# OctoSlime_Base_Unit_Light.net
KiCad netlist of a schematic drawn in EasyEDA Pro
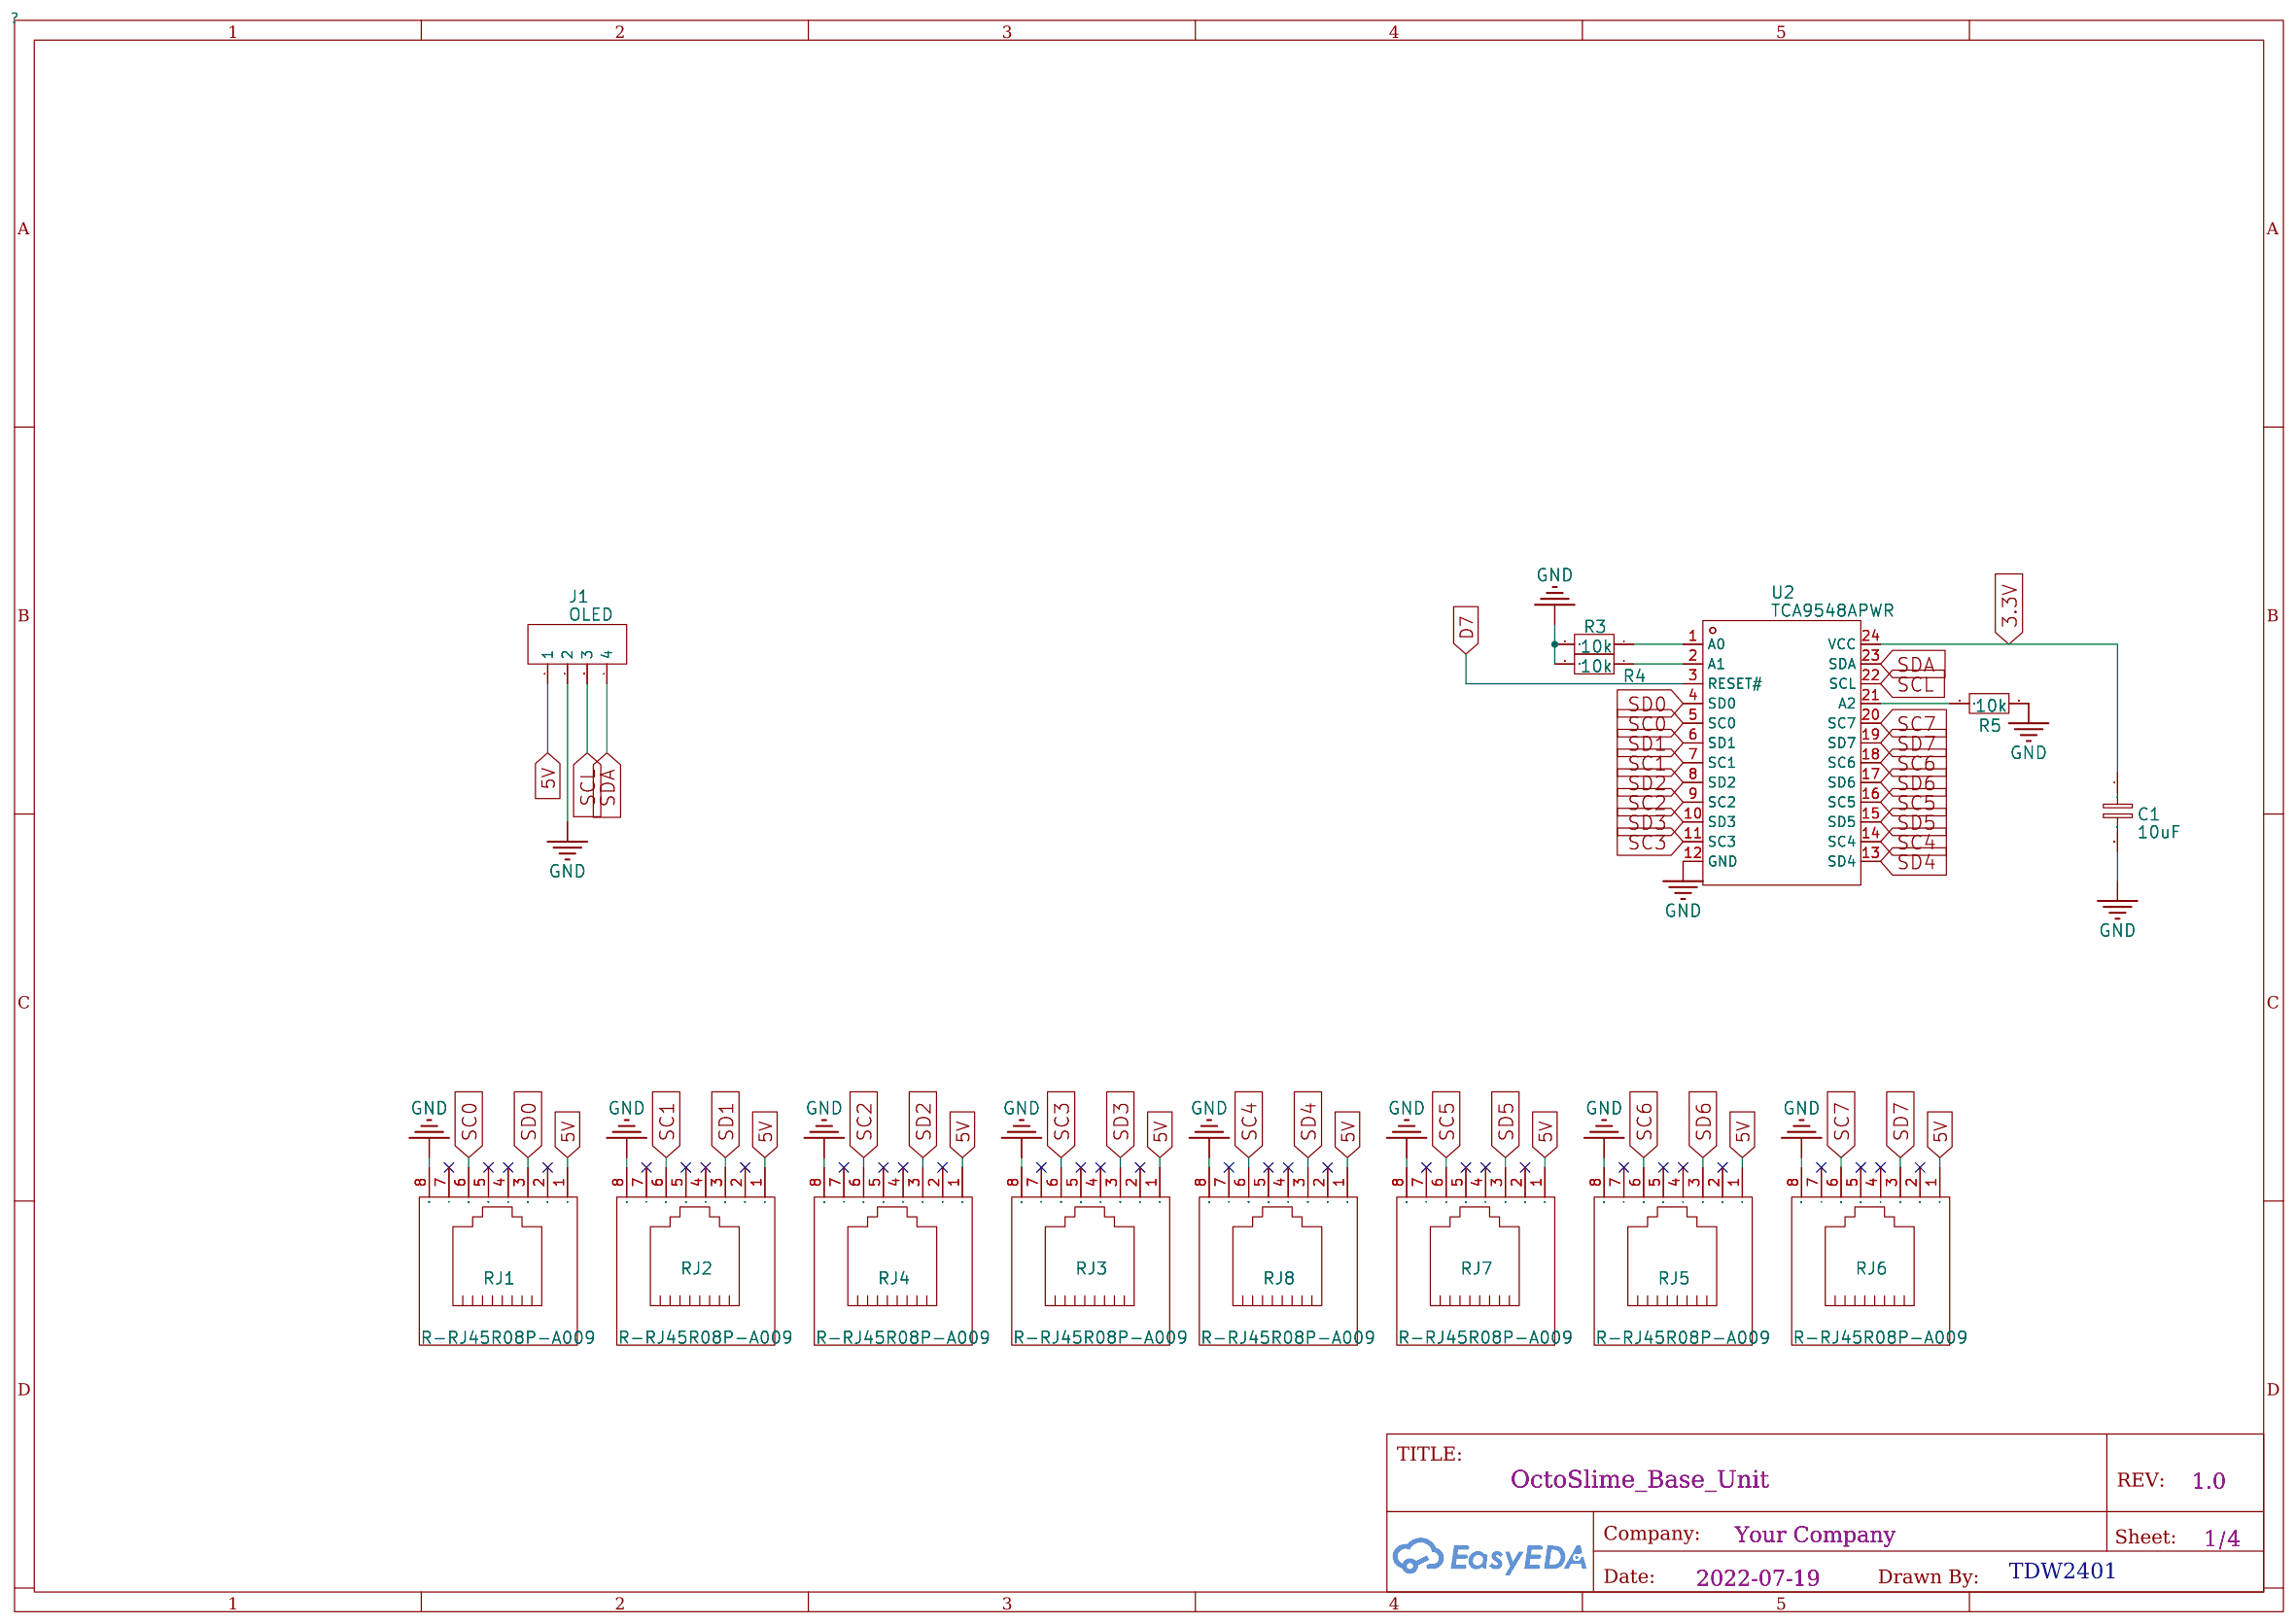
[diagram p0: I2C breakout and OLED]
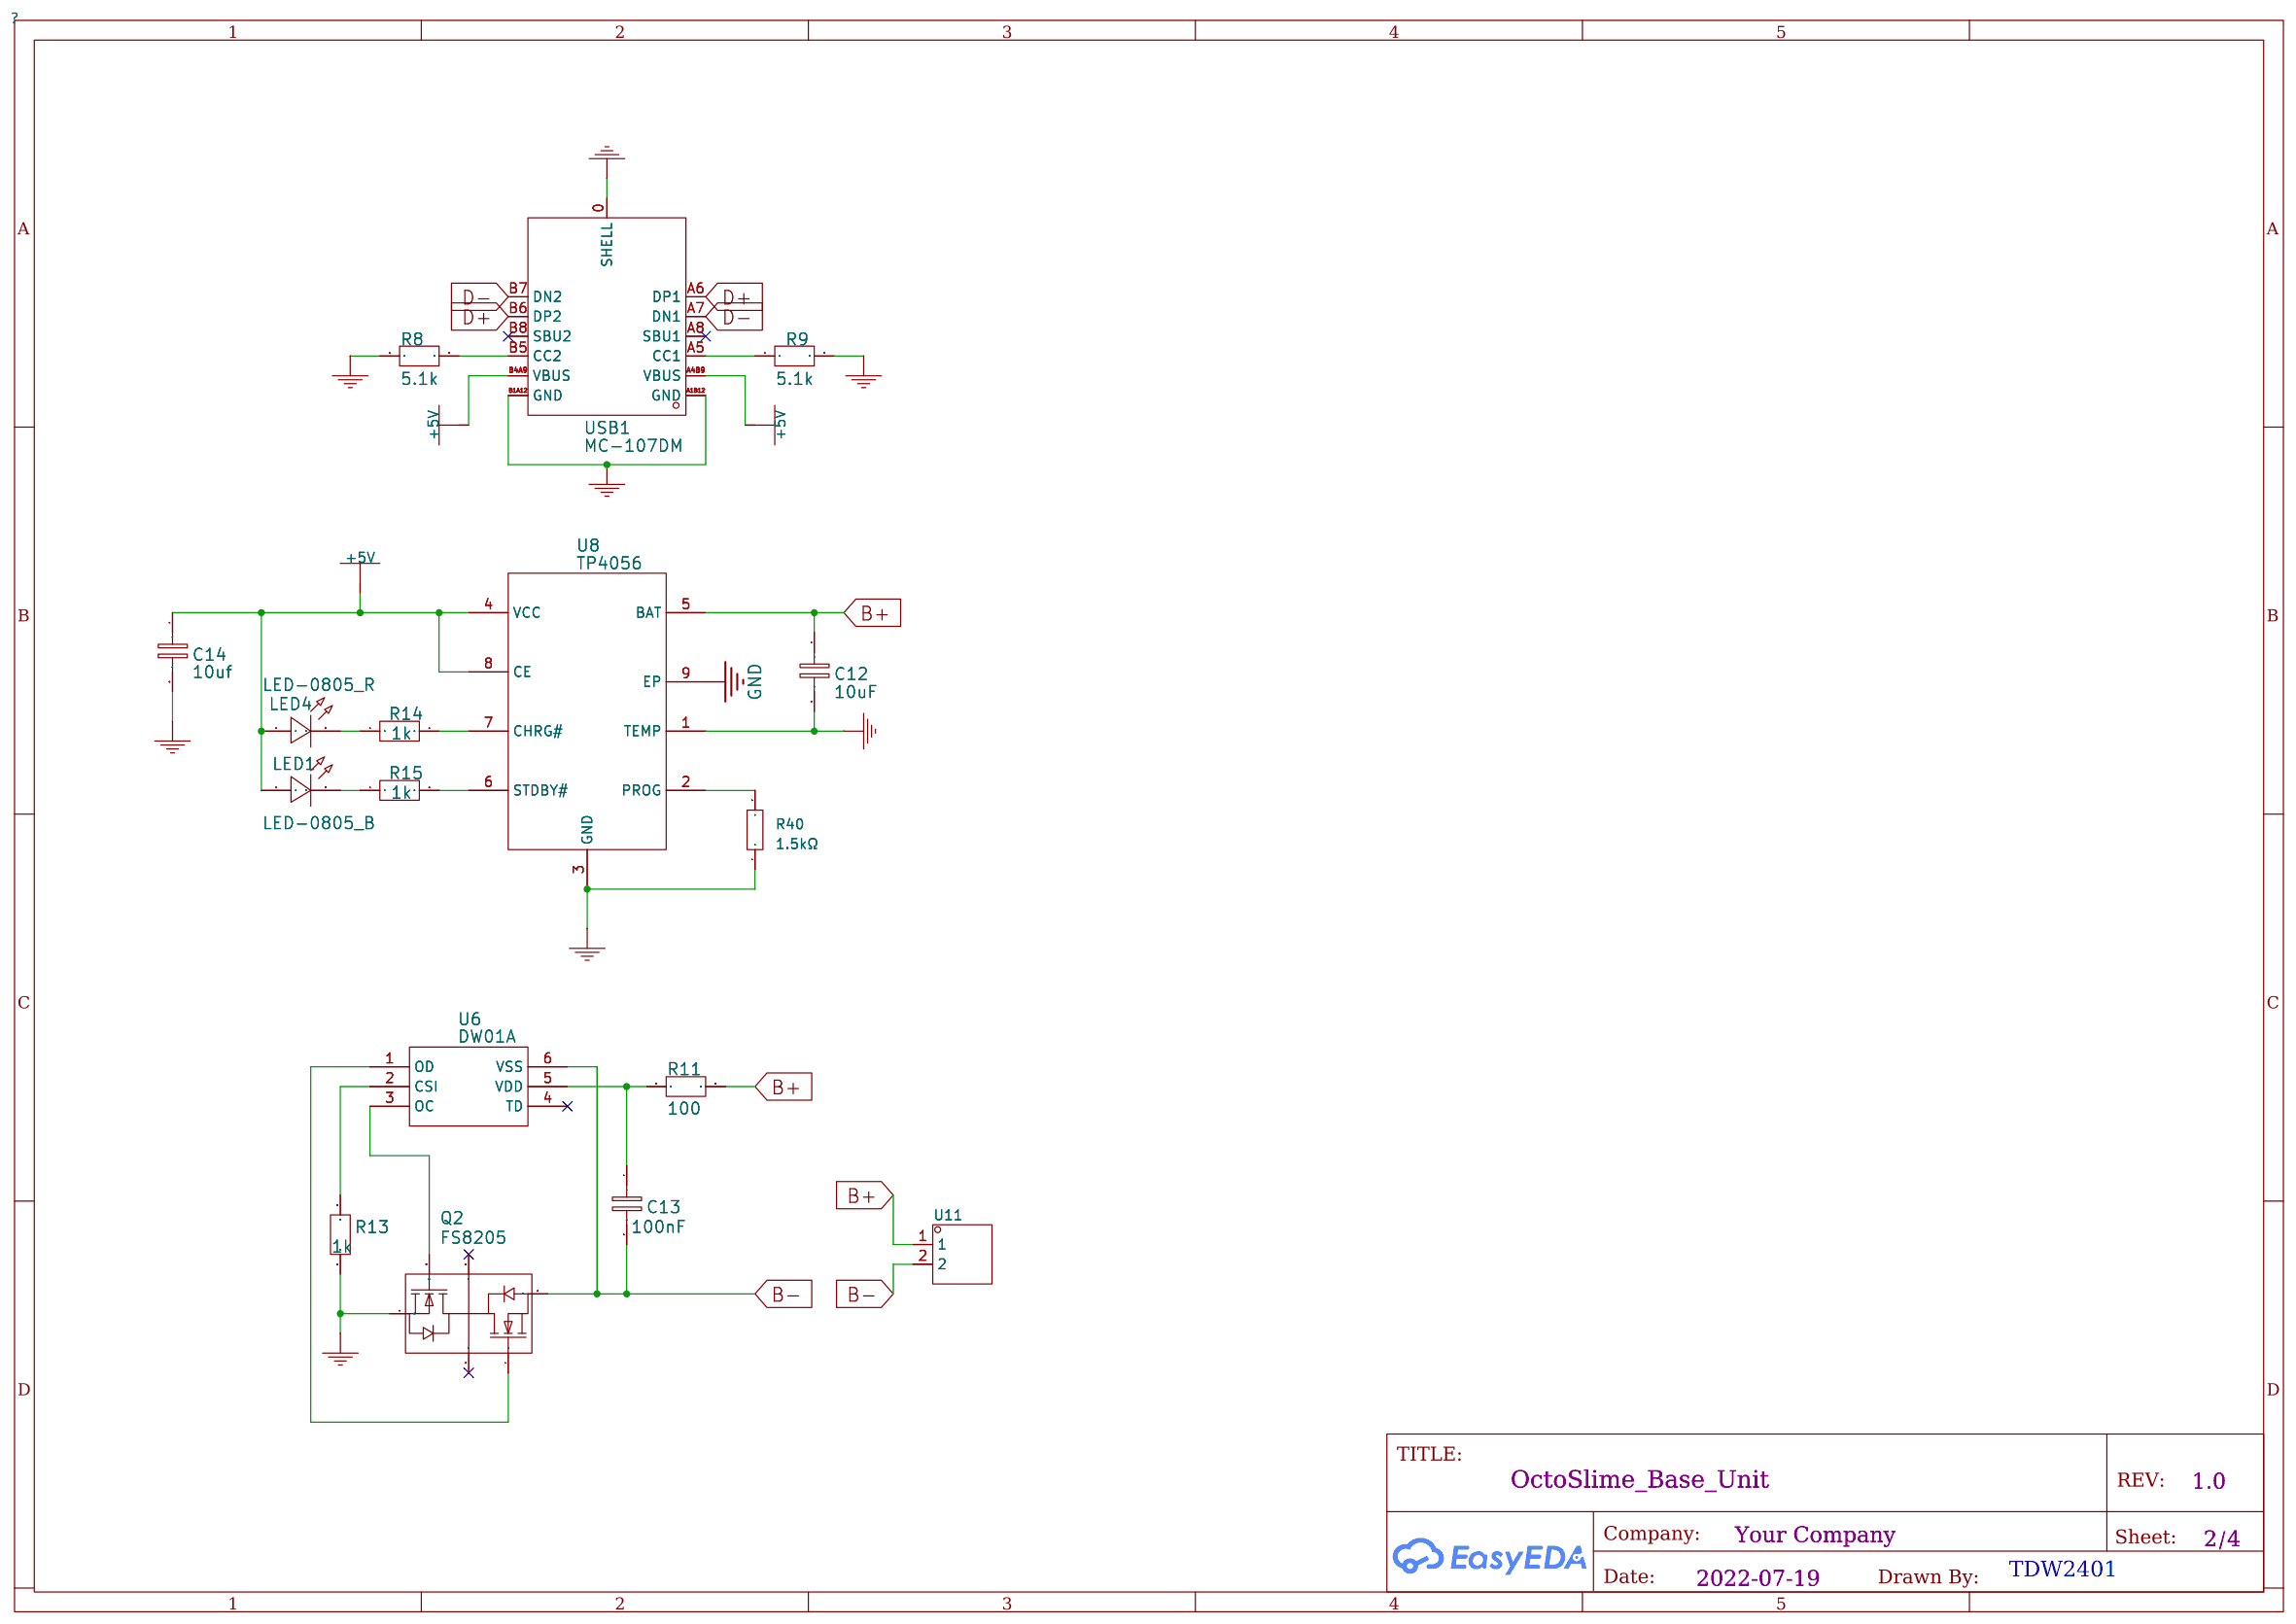
[diagram p1: Charge / data]
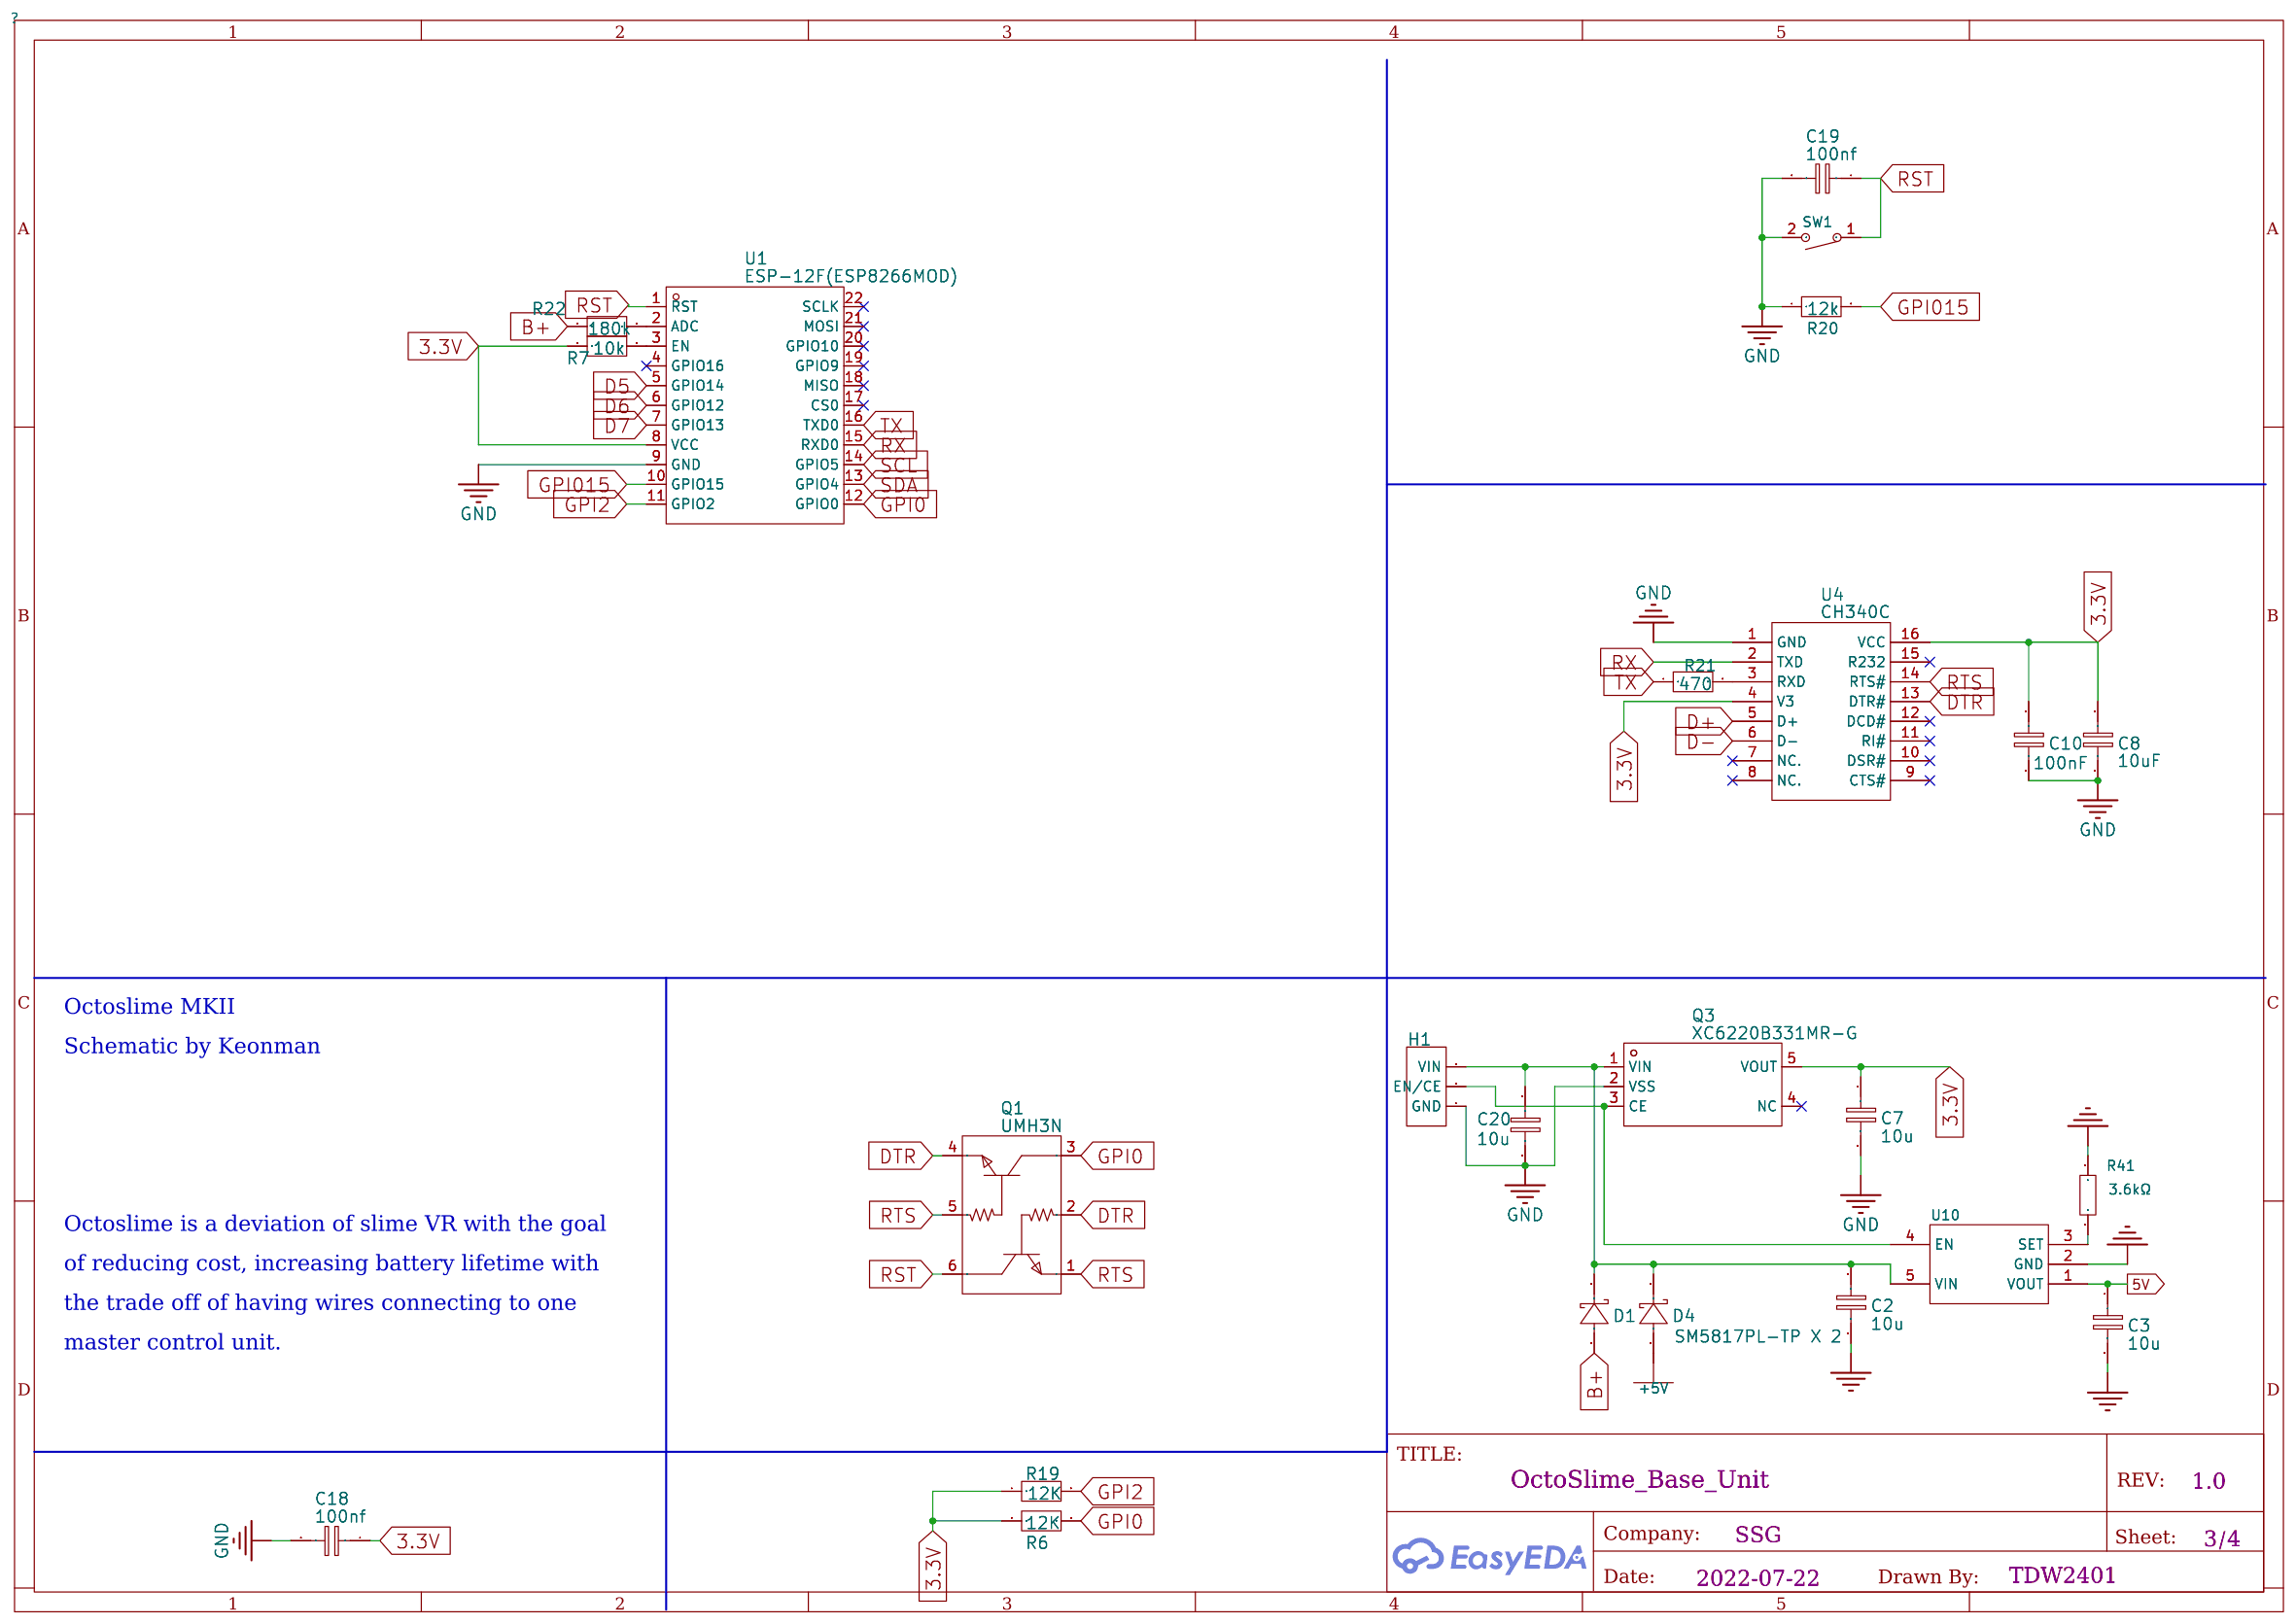
[diagram p2: MCU]
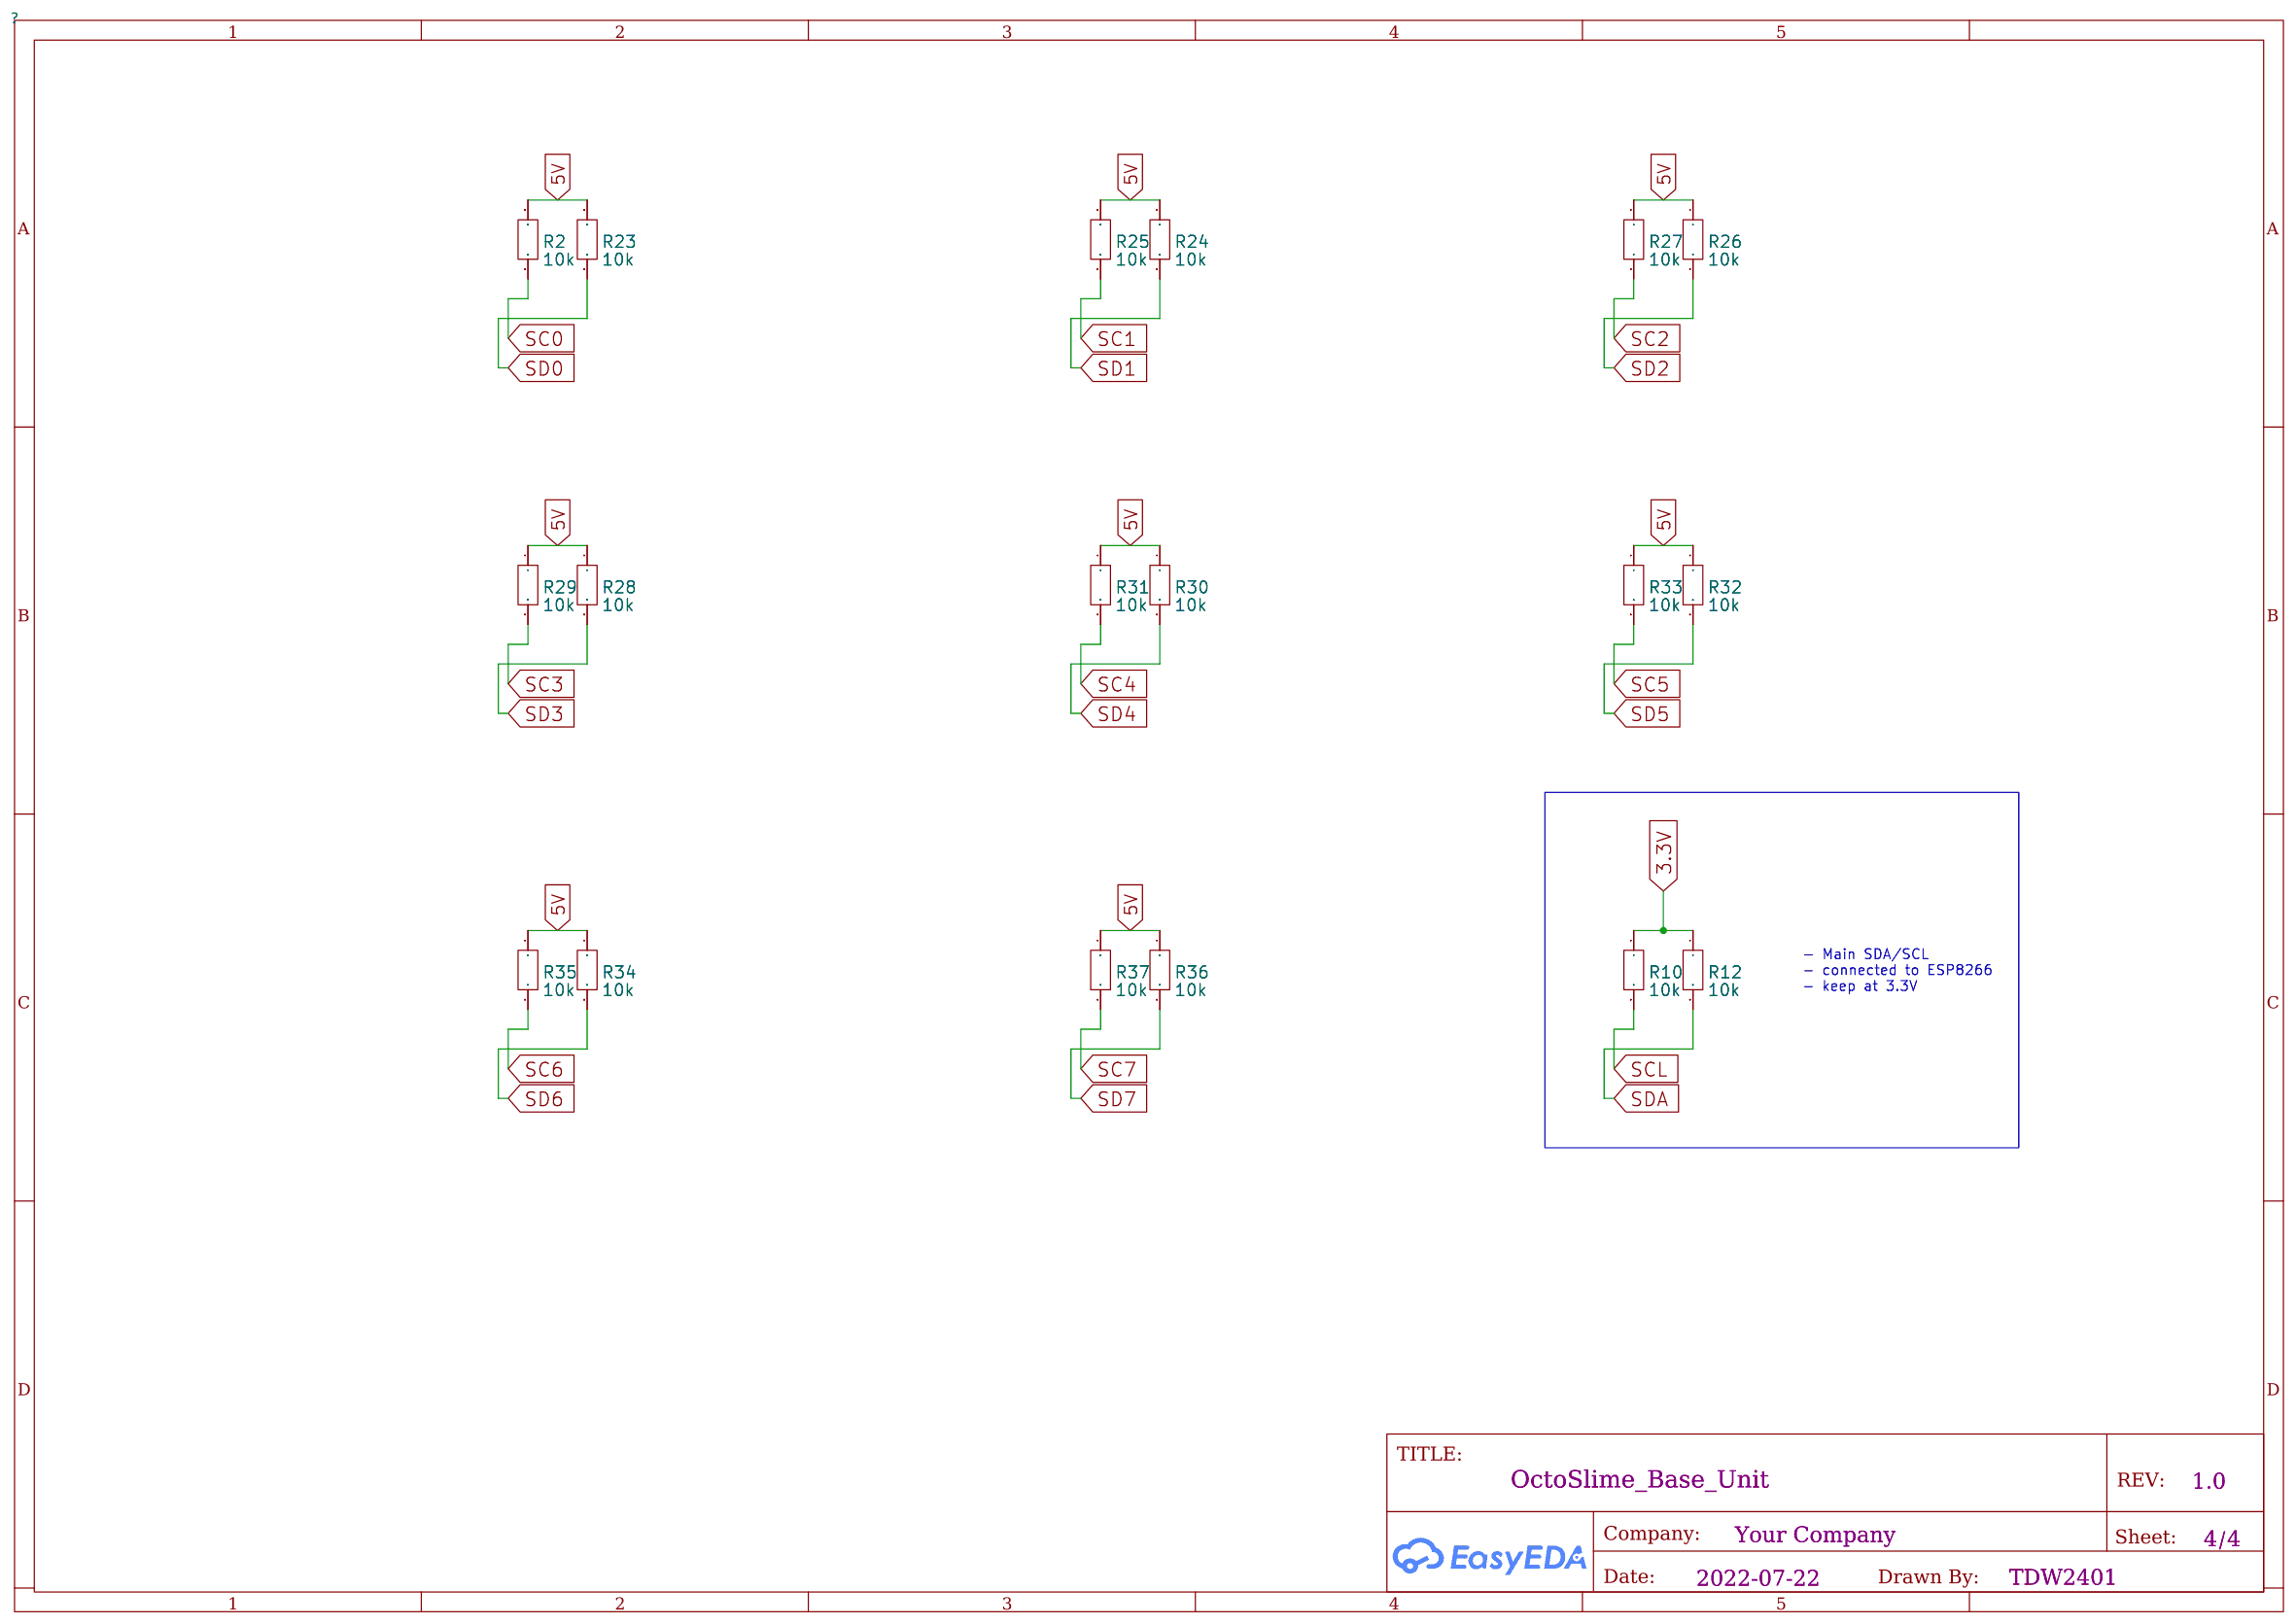
[diagram p3: I2C thing - ma - jigXC6220B331PR-G]

(export (version "E")
  (design (tool "Eeschema 10.0.6"))
  (components
    (comp (ref "C1")
      (value "10uF")
      (footprint "easyedapro:C0805")
      (libsource (lib "easyedapro") (part "10uF"))
    )
    (comp (ref "J1")
      (value "OLED")
      (footprint "easyedapro:HDR-M-2.54_1X4")
      (libsource (lib "easyedapro") (part "OLED"))
    )
    (comp (ref "R3") (value "10k") (footprint "easyedapro:R0805") (libsource (lib "easyedapro") (part "10k")))
    (comp (ref "R4") (value "10k") (footprint "easyedapro:R0805") (libsource (lib "easyedapro") (part "10k")))
    (comp (ref "R5") (value "10k") (footprint "easyedapro:R0805") (libsource (lib "easyedapro") (part "10k")))
    (comp (ref "RJ1")
      (value "R-RJ45R08P-A009")
      (footprint "easyedapro:RJ45-TH_R-RJ45R08P-A009")
      (fields (field (name "Manufacturer") "Ckmtw(灿科盟)"))
      (libsource (lib "easyedapro") (part "R-RJ45R08P-A009"))
    )
    (comp (ref "RJ2")
      (value "R-RJ45R08P-A009")
      (footprint "easyedapro:RJ45-TH_R-RJ45R08P-A009")
      (fields (field (name "Manufacturer") "Ckmtw(灿科盟)"))
      (libsource (lib "easyedapro") (part "R-RJ45R08P-A009"))
    )
    (comp (ref "RJ3")
      (value "R-RJ45R08P-A009")
      (footprint "easyedapro:RJ45-TH_R-RJ45R08P-A009")
      (fields (field (name "Manufacturer") "Ckmtw(灿科盟)"))
      (libsource (lib "easyedapro") (part "R-RJ45R08P-A009"))
    )
    (comp (ref "RJ4")
      (value "R-RJ45R08P-A009")
      (footprint "easyedapro:RJ45-TH_R-RJ45R08P-A009")
      (fields (field (name "Manufacturer") "Ckmtw(灿科盟)"))
      (libsource (lib "easyedapro") (part "R-RJ45R08P-A009"))
    )
    (comp (ref "RJ5")
      (value "R-RJ45R08P-A009")
      (footprint "easyedapro:RJ45-TH_R-RJ45R08P-A009")
      (fields (field (name "Manufacturer") "Ckmtw(灿科盟)"))
      (libsource (lib "easyedapro") (part "R-RJ45R08P-A009"))
    )
    (comp (ref "RJ6")
      (value "R-RJ45R08P-A009")
      (footprint "easyedapro:RJ45-TH_R-RJ45R08P-A009")
      (fields (field (name "Manufacturer") "Ckmtw(灿科盟)"))
      (libsource (lib "easyedapro") (part "R-RJ45R08P-A009"))
    )
    (comp (ref "RJ7")
      (value "R-RJ45R08P-A009")
      (footprint "easyedapro:RJ45-TH_R-RJ45R08P-A009")
      (fields (field (name "Manufacturer") "Ckmtw(灿科盟)"))
      (libsource (lib "easyedapro") (part "R-RJ45R08P-A009"))
    )
    (comp (ref "RJ8")
      (value "R-RJ45R08P-A009")
      (footprint "easyedapro:RJ45-TH_R-RJ45R08P-A009")
      (fields (field (name "Manufacturer") "Ckmtw(灿科盟)"))
      (libsource (lib "easyedapro") (part "R-RJ45R08P-A009"))
    )
    (comp (ref "U2")
      (value "TCA9548APWR")
      (footprint "easyedapro:TSSOP-24_L7.8-W4.4-P0.65-LS6.4-BL")
      (fields (field (name "Manufacturer") "TI"))
      (libsource (lib "easyedapro") (part "TCA9548APWR"))
    )
    (comp (ref "C12")
      (value "10uF")
      (footprint "easyedapro:C0805")
      (libsource (lib "easyedapro") (part "10uF"))
    )
    (comp (ref "C13")
      (value "100nF")
      (footprint "easyedapro:C0805")
      (libsource (lib "easyedapro") (part "100nF"))
    )
    (comp (ref "C14")
      (value "10uf")
      (footprint "easyedapro:C0805")
      (libsource (lib "easyedapro") (part "10uf"))
    )
    (comp (ref "LED1")
      (value "LED-0805_B")
      (footprint "easyedapro:LED0805_BLUE")
      (fields (field (name "Manufacturer Part") "D-B080508B1-KS2") (field (name "Manufacturer") "方舟 ARKLED"))
      (libsource (lib "easyedapro") (part "LED-0805_B"))
    )
    (comp (ref "LED4")
      (value "LED-0805_R")
      (footprint "easyedapro:LED0805_RED")
      (fields
        (field (name "Manufacturer Part") "17-21SURC/S530-A3/TR8")
        (field (name "Manufacturer") "EVERLIGHT(台湾亿光)")
      )
      (libsource (lib "easyedapro") (part "LED-0805_R"))
    )
    (comp (ref "Q2")
      (value "FS8205")
      (footprint "easyedapro:SOT-23-6_L2.9-W1.6-P0.95-LS2.8-BR")
      (fields (field (name "Manufacturer") "FORTUNE"))
      (libsource (lib "easyedapro") (part "FS8205"))
    )
    (comp (ref "R8")
      (value "5.1k")
      (footprint "easyedapro:R0805")
      (libsource (lib "easyedapro") (part "5.1k"))
    )
    (comp (ref "R9")
      (value "5.1k")
      (footprint "easyedapro:R0805")
      (libsource (lib "easyedapro") (part "5.1k"))
    )
    (comp (ref "R11")
      (value "100")
      (footprint "easyedapro:R0805")
      (libsource (lib "easyedapro") (part "100"))
    )
    (comp (ref "R13") (value "1k") (footprint "easyedapro:R0805") (libsource (lib "easyedapro") (part "1k")))
    (comp (ref "R14") (value "1k") (footprint "easyedapro:R0805") (libsource (lib "easyedapro") (part "1k")))
    (comp (ref "R15") (value "1k") (footprint "easyedapro:R0805") (libsource (lib "easyedapro") (part "1k")))
    (comp (ref "R40")
      (value "1.5kΩ")
      (footprint "easyedapro:R0805")
      (description "电阻类型:厚膜电阻;阻值:1.5kΩ;精度:±1%;功率:125mW;温度系数:±100ppm/;最大工作电压:150V;工作温度范围:-55~+155;")
      (fields
        (field (name "Manufacturer Part") "0805W8F1501T5E")
        (field (name "Manufacturer") "UNI-ROYAL(厚声)")
      )
      (libsource (lib "easyedapro") (part "0805W8F1501T5E"))
    )
    (comp (ref "U6")
      (value "DW01A")
      (footprint "easyedapro:SOT-23-6_L2.9-W1.6-P0.95-LS2.8-BL")
      (fields (field (name "Manufacturer") "FM"))
      (libsource (lib "easyedapro") (part "DW01A"))
    )
    (comp (ref "U8")
      (value "TP4056")
      (footprint "easyedapro:ESOP-8_L4.9-W3.9-P1.27-LS6.0-BL-EP")
      (fields (field (name "Manufacturer") "TOPPOWER"))
      (libsource (lib "easyedapro") (part "TP4056"))
    )
    (comp (ref "U11")
      (value "S2B-PH-K-S(LF)(SN)")
      (footprint "easyedapro:CONN-TH_S2B-PH-K-S-LF-SN")
      (description "参考系列:PH;间距:2mm;插针结构:1x2P;排数:1;每排PIN数:2;行距:-;安装方式:-;触头材质:黄铜;")
      (fields (field (name "Manufacturer") "JST"))
      (libsource (lib "easyedapro") (part "S2B-PH-K-S(LF)(SN)"))
    )
    (comp (ref "USB1")
      (value "MC-107DM")
      (footprint "easyedapro:USB-C-SMD_MC-107D")
      (fields (field (name "Manufacturer") "台湾汉博"))
      (libsource (lib "easyedapro") (part "MC-107DM"))
    )
    (comp (ref "C2") (value "10u") (footprint "easyedapro:C0805") (libsource (lib "easyedapro") (part "10u")))
    (comp (ref "C3") (value "10u") (footprint "easyedapro:C0805") (libsource (lib "easyedapro") (part "10u")))
    (comp (ref "C7") (value "10u") (footprint "easyedapro:C0805") (libsource (lib "easyedapro") (part "10u")))
    (comp (ref "C8")
      (value "10uF")
      (footprint "easyedapro:C0805")
      (libsource (lib "easyedapro") (part "10uF"))
    )
    (comp (ref "C10")
      (value "100nF")
      (footprint "easyedapro:C0805")
      (libsource (lib "easyedapro") (part "100nF"))
    )
    (comp (ref "C18")
      (value "100nf")
      (footprint "easyedapro:C0805")
      (libsource (lib "easyedapro") (part "100nf"))
    )
    (comp (ref "C19")
      (value "100nf")
      (footprint "easyedapro:C0805")
      (libsource (lib "easyedapro") (part "100nf"))
    )
    (comp (ref "C20")
      (value "10u")
      (footprint "easyedapro:C0805")
      (libsource (lib "easyedapro") (part "10u"))
    )
    (comp (ref "D1")
      (value "SM5817PL-TP X 2")
      (footprint "easyedapro:SOD-123FL_L2.8-W1.7-LS3.6-RD")
      (fields
        (field (name "Manufacturer Part") "SM5817PL-TP")
        (field (name "Manufacturer") "MCC(Micro Commercial Components)")
      )
      (libsource (lib "easyedapro") (part "SM5817PL-TP X 2"))
    )
    (comp (ref "D4")
      (value "SM5817PL-TP X 2")
      (footprint "easyedapro:SOD-123FL_L2.8-W1.7-LS3.6-RD")
      (fields
        (field (name "Manufacturer Part") "SM5817PL-TP")
        (field (name "Manufacturer") "MCC(Micro Commercial Components)")
      )
      (libsource (lib "easyedapro") (part "SM5817PL-TP X 2"))
    )
    (comp (ref "H1")
      (value "HDR-F-2.54_1x3")
      (footprint "easyedapro:HDR-F-2.54_1X3")
      (libsource (lib "easyedapro") (part "HDR-F-2.54_1x3"))
    )
    (comp (ref "Q1")
      (value "UMH3N")
      (footprint "easyedapro:SC-70-6_L2.2-W1.3-P0.65-LS2.1-BR")
      (fields (field (name "Manufacturer") "CJ"))
      (libsource (lib "easyedapro") (part "UMH3N"))
    )
    (comp (ref "Q3")
      (value "XC6220B331MR-G")
      (footprint "easyedapro:SOT-25-5_L3.0-W1.8-P0.95-LS3.0-BR")
      (fields (field (name "Manufacturer") "TOREX"))
      (libsource (lib "easyedapro") (part "XC6220B331MR-G"))
    )
    (comp (ref "R6") (value "12K") (footprint "easyedapro:R0805") (libsource (lib "easyedapro") (part "12K")))
    (comp (ref "R7") (value "10k") (footprint "easyedapro:R0805") (libsource (lib "easyedapro") (part "10k")))
    (comp (ref "R19")
      (value "12K")
      (footprint "easyedapro:R0805")
      (libsource (lib "easyedapro") (part "12K"))
    )
    (comp (ref "R20")
      (value "12k")
      (footprint "easyedapro:R0805")
      (libsource (lib "easyedapro") (part "12k"))
    )
    (comp (ref "R21")
      (value "470")
      (footprint "easyedapro:R0805")
      (libsource (lib "easyedapro") (part "470"))
    )
    (comp (ref "R22")
      (value "180k")
      (footprint "easyedapro:R0805")
      (libsource (lib "easyedapro") (part "180k"))
    )
    (comp (ref "R41")
      (value "3.6kΩ")
      (footprint "easyedapro:R0805")
      (description "电阻类型:厚膜电阻;阻值:3.6kΩ;精度:±1%;功率:1/8W;温度系数:±100ppm/;最大工作电压:150V;工作温度范围:-55~+155;")
      (fields
        (field (name "Manufacturer Part") "0805W8F3601T5E")
        (field (name "Manufacturer") "UNI-ROYAL(厚声)")
      )
      (libsource (lib "easyedapro") (part "0805W8F3601T5E"))
    )
    (comp (ref "SW1")
      (value "~")
      (footprint "easyedapro:SW-SMD_L4.0-W2.9-LS5.0")
      (fields (field (name "Manufacturer Part") "TS342A2P-WZ") (field (name "Manufacturer") "SHOU HAN(首韩)"))
      (libsource (lib "easyedapro") (part "TS342A2P-WZ"))
    )
    (comp (ref "U1")
      (value "ESP-12F(ESP8266MOD)")
      (footprint "easyedapro:WIFIM-SMD_ESP-12F-ESP8266MOD")
      (fields (field (name "Manufacturer") "Ai-Thinker"))
      (libsource (lib "easyedapro") (part "ESP-12F(ESP8266MOD)"))
    )
    (comp (ref "U4")
      (value "CH340C")
      (footprint "easyedapro:SOP-16_L10.0-W3.9-P1.27-LS6.0-BL")
      (fields (field (name "Manufacturer") "WCH"))
      (libsource (lib "easyedapro") (part "CH340C"))
    )
    (comp (ref "U10")
      (value "MT9700")
      (footprint "easyedapro:SOT-23-5_L3.0-W1.7-P0.95-LS2.8-BR")
      (description "低功耗负载开关/USB电源开关/限流保护开关")
      (fields (field (name "Manufacturer") "西安航天民芯"))
      (libsource (lib "easyedapro") (part "MT9700"))
    )
    (comp (ref "R2") (value "10k") (footprint "easyedapro:R0805") (libsource (lib "easyedapro") (part "10k")))
    (comp (ref "R10")
      (value "10k")
      (footprint "easyedapro:R0805")
      (libsource (lib "easyedapro") (part "10k"))
    )
    (comp (ref "R12")
      (value "10k")
      (footprint "easyedapro:R0805")
      (libsource (lib "easyedapro") (part "10k"))
    )
    (comp (ref "R23")
      (value "10k")
      (footprint "easyedapro:R0805")
      (libsource (lib "easyedapro") (part "10k"))
    )
    (comp (ref "R24")
      (value "10k")
      (footprint "easyedapro:R0805")
      (libsource (lib "easyedapro") (part "10k"))
    )
    (comp (ref "R25")
      (value "10k")
      (footprint "easyedapro:R0805")
      (libsource (lib "easyedapro") (part "10k"))
    )
    (comp (ref "R26")
      (value "10k")
      (footprint "easyedapro:R0805")
      (libsource (lib "easyedapro") (part "10k"))
    )
    (comp (ref "R27")
      (value "10k")
      (footprint "easyedapro:R0805")
      (libsource (lib "easyedapro") (part "10k"))
    )
    (comp (ref "R28")
      (value "10k")
      (footprint "easyedapro:R0805")
      (libsource (lib "easyedapro") (part "10k"))
    )
    (comp (ref "R29")
      (value "10k")
      (footprint "easyedapro:R0805")
      (libsource (lib "easyedapro") (part "10k"))
    )
    (comp (ref "R30")
      (value "10k")
      (footprint "easyedapro:R0805")
      (libsource (lib "easyedapro") (part "10k"))
    )
    (comp (ref "R31")
      (value "10k")
      (footprint "easyedapro:R0805")
      (libsource (lib "easyedapro") (part "10k"))
    )
    (comp (ref "R32")
      (value "10k")
      (footprint "easyedapro:R0805")
      (libsource (lib "easyedapro") (part "10k"))
    )
    (comp (ref "R33")
      (value "10k")
      (footprint "easyedapro:R0805")
      (libsource (lib "easyedapro") (part "10k"))
    )
    (comp (ref "R34")
      (value "10k")
      (footprint "easyedapro:R0805")
      (libsource (lib "easyedapro") (part "10k"))
    )
    (comp (ref "R35")
      (value "10k")
      (footprint "easyedapro:R0805")
      (libsource (lib "easyedapro") (part "10k"))
    )
    (comp (ref "R36")
      (value "10k")
      (footprint "easyedapro:R0805")
      (libsource (lib "easyedapro") (part "10k"))
    )
    (comp (ref "R37")
      (value "10k")
      (footprint "easyedapro:R0805")
      (libsource (lib "easyedapro") (part "10k"))
    )
  )
  (nets
    (net (code "1") (name "+5V") (class "Default")
      (node (ref "C14") (pin "1") (pinfunction "1_1") (pintype "input"))
      (node (ref "D4") (pin "2") (pinfunction "A_2") (pintype "input"))
      (node (ref "LED1") (pin "1") (pinfunction "1_1") (pintype "input"))
      (node (ref "LED4") (pin "1") (pinfunction "1_1") (pintype "input"))
      (node (ref "U8") (pin "4") (pinfunction "VCC_4") (pintype "input"))
      (node (ref "U8") (pin "8") (pinfunction "CE_8") (pintype "input"))
      (node (ref "USB1") (pin "A4B9") (pinfunction "VBUS_A4B9") (pintype "input"))
      (node (ref "USB1") (pin "B4A9") (pinfunction "VBUS_B4A9") (pintype "input"))
    )
    (net (code "2") (name "3.3V") (class "Default")
      (node (ref "C1") (pin "1") (pinfunction "1_1") (pintype "input"))
      (node (ref "C10") (pin "1") (pinfunction "1_1") (pintype "input"))
      (node (ref "C18") (pin "1") (pinfunction "1_1") (pintype "input"))
      (node (ref "C7") (pin "1") (pinfunction "1_1") (pintype "input"))
      (node (ref "C8") (pin "1") (pinfunction "1_1") (pintype "input"))
      (node (ref "Q3") (pin "5") (pinfunction "VOUT_5") (pintype "input"))
      (node (ref "R10") (pin "1") (pinfunction "1_1") (pintype "input"))
      (node (ref "R12") (pin "1") (pinfunction "1_1") (pintype "input"))
      (node (ref "R19") (pin "1") (pinfunction "1_1") (pintype "input"))
      (node (ref "R6") (pin "1") (pinfunction "1_1") (pintype "input"))
      (node (ref "R7") (pin "1") (pinfunction "1_1") (pintype "input"))
      (node (ref "U1") (pin "8") (pinfunction "VCC_8") (pintype "input"))
      (node (ref "U2") (pin "24") (pinfunction "VCC_24") (pintype "input"))
      (node (ref "U4") (pin "16") (pinfunction "VCC_16") (pintype "input"))
      (node (ref "U4") (pin "4") (pinfunction "V3_4") (pintype "input"))
    )
    (net (code "3") (name "5V") (class "Default")
      (node (ref "C3") (pin "1") (pinfunction "1_1") (pintype "input"))
      (node (ref "J1") (pin "1") (pinfunction "1_1") (pintype "input"))
      (node (ref "R2") (pin "1") (pinfunction "1_1") (pintype "input"))
      (node (ref "R23") (pin "1") (pinfunction "1_1") (pintype "input"))
      (node (ref "R24") (pin "1") (pinfunction "1_1") (pintype "input"))
      (node (ref "R25") (pin "1") (pinfunction "1_1") (pintype "input"))
      (node (ref "R26") (pin "1") (pinfunction "1_1") (pintype "input"))
      (node (ref "R27") (pin "1") (pinfunction "1_1") (pintype "input"))
      (node (ref "R28") (pin "1") (pinfunction "1_1") (pintype "input"))
      (node (ref "R29") (pin "1") (pinfunction "1_1") (pintype "input"))
      (node (ref "R30") (pin "1") (pinfunction "1_1") (pintype "input"))
      (node (ref "R31") (pin "1") (pinfunction "1_1") (pintype "input"))
      (node (ref "R32") (pin "1") (pinfunction "1_1") (pintype "input"))
      (node (ref "R33") (pin "1") (pinfunction "1_1") (pintype "input"))
      (node (ref "R34") (pin "1") (pinfunction "1_1") (pintype "input"))
      (node (ref "R35") (pin "1") (pinfunction "1_1") (pintype "input"))
      (node (ref "R36") (pin "1") (pinfunction "1_1") (pintype "input"))
      (node (ref "R37") (pin "1") (pinfunction "1_1") (pintype "input"))
      (node (ref "RJ1") (pin "1") (pinfunction "1_1") (pintype "input"))
      (node (ref "RJ2") (pin "1") (pinfunction "1_1") (pintype "input"))
      (node (ref "RJ3") (pin "1") (pinfunction "1_1") (pintype "input"))
      (node (ref "RJ4") (pin "1") (pinfunction "1_1") (pintype "input"))
      (node (ref "RJ5") (pin "1") (pinfunction "1_1") (pintype "input"))
      (node (ref "RJ6") (pin "1") (pinfunction "1_1") (pintype "input"))
      (node (ref "RJ7") (pin "1") (pinfunction "1_1") (pintype "input"))
      (node (ref "RJ8") (pin "1") (pinfunction "1_1") (pintype "input"))
      (node (ref "U10") (pin "1") (pinfunction "VOUT_1") (pintype "input"))
    )
    (net (code "4") (name "B+") (class "Default")
      (node (ref "C12") (pin "1") (pinfunction "1_1") (pintype "input"))
      (node (ref "D1") (pin "2") (pinfunction "A_2") (pintype "input"))
      (node (ref "R11") (pin "2") (pinfunction "2_2") (pintype "input"))
      (node (ref "R22") (pin "1") (pinfunction "1_1") (pintype "input"))
      (node (ref "U11") (pin "1") (pinfunction "1_1") (pintype "input"))
      (node (ref "U8") (pin "5") (pinfunction "BAT_5") (pintype "input"))
    )
    (net (code "5") (name "B-") (class "Default")
      (node (ref "C13") (pin "2") (pinfunction "2_2") (pintype "input"))
      (node (ref "Q2") (pin "3") (pinfunction "S2_3") (pintype "input"))
      (node (ref "U11") (pin "2") (pinfunction "2_2") (pintype "input"))
      (node (ref "U6") (pin "6") (pinfunction "VSS_6") (pintype "input"))
    )
    (net (code "6") (name "D+") (class "Default")
      (node (ref "U4") (pin "5") (pinfunction "D+_5") (pintype "input"))
      (node (ref "USB1") (pin "A6") (pinfunction "DP1_A6") (pintype "input"))
      (node (ref "USB1") (pin "B6") (pinfunction "DP2_B6") (pintype "input"))
    )
    (net (code "7") (name "D-") (class "Default")
      (node (ref "U4") (pin "6") (pinfunction "D-_6") (pintype "input"))
      (node (ref "USB1") (pin "A7") (pinfunction "DN1_A7") (pintype "input"))
      (node (ref "USB1") (pin "B7") (pinfunction "DN2_B7") (pintype "input"))
    )
    (net (code "8") (name "D5") (class "Default")
      (node (ref "U1") (pin "5") (pinfunction "GPIO14_5") (pintype "input"))
    )
    (net (code "9") (name "D6") (class "Default")
      (node (ref "U1") (pin "6") (pinfunction "GPIO12_6") (pintype "input"))
    )
    (net (code "10") (name "D7") (class "Default")
      (node (ref "U1") (pin "7") (pinfunction "GPIO13_7") (pintype "input"))
      (node (ref "U2") (pin "3") (pinfunction "RESET#_3") (pintype "input"))
    )
    (net (code "11") (name "DTR") (class "Default")
      (node (ref "Q1") (pin "2") (pinfunction "B_2") (pintype "input"))
      (node (ref "Q1") (pin "4") (pinfunction "E_4") (pintype "input"))
      (node (ref "U4") (pin "13") (pinfunction "DTR#_13") (pintype "input"))
    )
    (net (code "12") (name "GND") (class "Default")
      (node (ref "C1") (pin "2") (pinfunction "2_2") (pintype "input"))
      (node (ref "C10") (pin "2") (pinfunction "2_2") (pintype "input"))
      (node (ref "C12") (pin "2") (pinfunction "2_2") (pintype "input"))
      (node (ref "C14") (pin "2") (pinfunction "2_2") (pintype "input"))
      (node (ref "C18") (pin "2") (pinfunction "2_2") (pintype "input"))
      (node (ref "C19") (pin "2") (pinfunction "2_2") (pintype "input"))
      (node (ref "C2") (pin "2") (pinfunction "2_2") (pintype "input"))
      (node (ref "C20") (pin "2") (pinfunction "2_2") (pintype "input"))
      (node (ref "C3") (pin "2") (pinfunction "2_2") (pintype "input"))
      (node (ref "C7") (pin "2") (pinfunction "2_2") (pintype "input"))
      (node (ref "C8") (pin "2") (pinfunction "2_2") (pintype "input"))
      (node (ref "H1") (pin "1") (pinfunction "GND_1") (pintype "input"))
      (node (ref "J1") (pin "2") (pinfunction "2_2") (pintype "input"))
      (node (ref "Q2") (pin "1") (pinfunction "S1_1") (pintype "input"))
      (node (ref "Q3") (pin "2") (pinfunction "VSS_2") (pintype "input"))
      (node (ref "R13") (pin "2") (pinfunction "2_2") (pintype "input"))
      (node (ref "R20") (pin "1") (pinfunction "1_1") (pintype "input"))
      (node (ref "R3") (pin "2") (pinfunction "2_2") (pintype "input"))
      (node (ref "R4") (pin "2") (pinfunction "2_2") (pintype "input"))
      (node (ref "R40") (pin "1") (pinfunction "1_1") (pintype "input"))
      (node (ref "R41") (pin "2") (pinfunction "2_2") (pintype "input"))
      (node (ref "R5") (pin "1") (pinfunction "1_1") (pintype "input"))
      (node (ref "R8") (pin "1") (pinfunction "1_1") (pintype "input"))
      (node (ref "R9") (pin "2") (pinfunction "2_2") (pintype "input"))
      (node (ref "RJ1") (pin "8") (pinfunction "8_8") (pintype "input"))
      (node (ref "RJ2") (pin "8") (pinfunction "8_8") (pintype "input"))
      (node (ref "RJ3") (pin "8") (pinfunction "8_8") (pintype "input"))
      (node (ref "RJ4") (pin "8") (pinfunction "8_8") (pintype "input"))
      (node (ref "RJ5") (pin "8") (pinfunction "8_8") (pintype "input"))
      (node (ref "RJ6") (pin "8") (pinfunction "8_8") (pintype "input"))
      (node (ref "RJ7") (pin "8") (pinfunction "8_8") (pintype "input"))
      (node (ref "RJ8") (pin "8") (pinfunction "8_8") (pintype "input"))
      (node (ref "SW1") (pin "2") (pinfunction "2_2") (pintype "input"))
      (node (ref "U1") (pin "9") (pinfunction "GND_9") (pintype "input"))
      (node (ref "U10") (pin "2") (pinfunction "GND_2") (pintype "input"))
      (node (ref "U2") (pin "12") (pinfunction "GND_12") (pintype "input"))
      (node (ref "U4") (pin "1") (pinfunction "GND_1") (pintype "input"))
      (node (ref "U8") (pin "1") (pinfunction "TEMP_1") (pintype "input"))
      (node (ref "U8") (pin "3") (pinfunction "GND_3") (pintype "input"))
      (node (ref "U8") (pin "9") (pinfunction "EP_9") (pintype "input"))
      (node (ref "USB1") (pin "0") (pinfunction "SHELL_0") (pintype "input"))
      (node (ref "USB1") (pin "A1B12") (pinfunction "GND_A1B12") (pintype "input"))
      (node (ref "USB1") (pin "B1A12") (pinfunction "GND_B1A12") (pintype "input"))
    )
    (net (code "13") (name "GPI0") (class "Default")
      (node (ref "Q1") (pin "3") (pinfunction "C_3") (pintype "input"))
      (node (ref "R6") (pin "2") (pinfunction "2_2") (pintype "input"))
      (node (ref "U1") (pin "12") (pinfunction "GPIO0_12") (pintype "input"))
    )
    (net (code "14") (name "GPI2") (class "Default")
      (node (ref "R19") (pin "2") (pinfunction "2_2") (pintype "input"))
      (node (ref "U1") (pin "11") (pinfunction "GPIO2_11") (pintype "input"))
    )
    (net (code "15") (name "GPI015") (class "Default")
      (node (ref "R20") (pin "2") (pinfunction "2_2") (pintype "input"))
      (node (ref "U1") (pin "10") (pinfunction "GPIO15_10") (pintype "input"))
    )
    (net (code "16") (name "Net-(D1-C)") (class "Default")
      (node (ref "C2") (pin "1") (pinfunction "1_1") (pintype "input"))
      (node (ref "C20") (pin "1") (pinfunction "1_1") (pintype "input"))
      (node (ref "D1") (pin "1") (pinfunction "C_1") (pintype "input"))
      (node (ref "D4") (pin "1") (pinfunction "C_1") (pintype "input"))
      (node (ref "H1") (pin "3") (pinfunction "VIN_3") (pintype "input"))
      (node (ref "Q3") (pin "1") (pinfunction "VIN_1") (pintype "input"))
      (node (ref "U10") (pin "5") (pinfunction "VIN_5") (pintype "input"))
    )
    (net (code "17") (name "Net-(H1-EN{slash}CE)") (class "Default")
      (node (ref "H1") (pin "2") (pinfunction "EN/CE_2") (pintype "input"))
      (node (ref "Q3") (pin "3") (pinfunction "CE_3") (pintype "input"))
      (node (ref "U10") (pin "4") (pinfunction "EN_4") (pintype "input"))
    )
    (net (code "18") (name "Net-(LED1-Pad2)") (class "Default")
      (node (ref "LED1") (pin "2") (pinfunction "2_2") (pintype "input"))
      (node (ref "R15") (pin "1") (pinfunction "1_1") (pintype "input"))
    )
    (net (code "19") (name "Net-(LED4-Pad2)") (class "Default")
      (node (ref "LED4") (pin "2") (pinfunction "2_2") (pintype "input"))
      (node (ref "R14") (pin "1") (pinfunction "1_1") (pintype "input"))
    )
    (net (code "20") (name "Net-(Q2-G1)") (class "Default")
      (node (ref "Q2") (pin "6") (pinfunction "G1_6") (pintype "input"))
      (node (ref "U6") (pin "3") (pinfunction "OC_3") (pintype "input"))
    )
    (net (code "21") (name "Net-(Q2-G2)") (class "Default")
      (node (ref "Q2") (pin "4") (pinfunction "G2_4") (pintype "input"))
      (node (ref "U6") (pin "1") (pinfunction "OD_1") (pintype "input"))
    )
    (net (code "22") (name "Net-(U1-ADC)") (class "Default")
      (node (ref "R22") (pin "2") (pinfunction "2_2") (pintype "input"))
      (node (ref "U1") (pin "2") (pinfunction "ADC_2") (pintype "input"))
    )
    (net (code "23") (name "Net-(U1-EN)") (class "Default")
      (node (ref "R7") (pin "2") (pinfunction "2_2") (pintype "input"))
      (node (ref "U1") (pin "3") (pinfunction "EN_3") (pintype "input"))
    )
    (net (code "24") (name "Net-(U2-A0)") (class "Default")
      (node (ref "R3") (pin "1") (pinfunction "1_1") (pintype "input"))
      (node (ref "U2") (pin "1") (pinfunction "A0_1") (pintype "input"))
    )
    (net (code "25") (name "Net-(U2-A1)") (class "Default")
      (node (ref "R4") (pin "1") (pinfunction "1_1") (pintype "input"))
      (node (ref "U2") (pin "2") (pinfunction "A1_2") (pintype "input"))
    )
    (net (code "26") (name "Net-(U2-A2)") (class "Default")
      (node (ref "R5") (pin "2") (pinfunction "2_2") (pintype "input"))
      (node (ref "U2") (pin "21") (pinfunction "A2_21") (pintype "input"))
    )
    (net (code "27") (name "Net-(U4-RXD)") (class "Default")
      (node (ref "R21") (pin "2") (pinfunction "2_2") (pintype "input"))
      (node (ref "U4") (pin "3") (pinfunction "RXD_3") (pintype "input"))
    )
    (net (code "28") (name "Net-(U6-CSI)") (class "Default")
      (node (ref "R13") (pin "1") (pinfunction "1_1") (pintype "input"))
      (node (ref "U6") (pin "2") (pinfunction "CSI_2") (pintype "input"))
    )
    (net (code "29") (name "Net-(U6-VDD)") (class "Default")
      (node (ref "C13") (pin "1") (pinfunction "1_1") (pintype "input"))
      (node (ref "R11") (pin "1") (pinfunction "1_1") (pintype "input"))
      (node (ref "U6") (pin "5") (pinfunction "VDD_5") (pintype "input"))
    )
    (net (code "30") (name "Net-(U8-CHRG#)") (class "Default")
      (node (ref "R14") (pin "2") (pinfunction "2_2") (pintype "input"))
      (node (ref "U8") (pin "7") (pinfunction "CHRG#_7") (pintype "input"))
    )
    (net (code "31") (name "Net-(U8-PROG)") (class "Default")
      (node (ref "R40") (pin "2") (pinfunction "2_2") (pintype "input"))
      (node (ref "U8") (pin "2") (pinfunction "PROG_2") (pintype "input"))
    )
    (net (code "32") (name "Net-(U8-STDBY#)") (class "Default")
      (node (ref "R15") (pin "2") (pinfunction "2_2") (pintype "input"))
      (node (ref "U8") (pin "6") (pinfunction "STDBY#_6") (pintype "input"))
    )
    (net (code "33") (name "Net-(U10-SET)") (class "Default")
      (node (ref "R41") (pin "1") (pinfunction "1_1") (pintype "input"))
      (node (ref "U10") (pin "3") (pinfunction "SET_3") (pintype "input"))
    )
    (net (code "34") (name "Net-(USB1-CC1)") (class "Default")
      (node (ref "R9") (pin "1") (pinfunction "1_1") (pintype "input"))
      (node (ref "USB1") (pin "A5") (pinfunction "CC1_A5") (pintype "input"))
    )
    (net (code "35") (name "Net-(USB1-CC2)") (class "Default")
      (node (ref "R8") (pin "2") (pinfunction "2_2") (pintype "input"))
      (node (ref "USB1") (pin "B5") (pinfunction "CC2_B5") (pintype "input"))
    )
    (net (code "36") (name "RST") (class "Default")
      (node (ref "C19") (pin "1") (pinfunction "1_1") (pintype "input"))
      (node (ref "Q1") (pin "6") (pinfunction "C_6") (pintype "input"))
      (node (ref "SW1") (pin "1") (pinfunction "1_1") (pintype "input"))
      (node (ref "U1") (pin "1") (pinfunction "RST_1") (pintype "input"))
    )
    (net (code "37") (name "RTS") (class "Default")
      (node (ref "Q1") (pin "1") (pinfunction "E_1") (pintype "input"))
      (node (ref "Q1") (pin "5") (pinfunction "B_5") (pintype "input"))
      (node (ref "U4") (pin "14") (pinfunction "RTS#_14") (pintype "input"))
    )
    (net (code "38") (name "RX") (class "Default")
      (node (ref "U1") (pin "15") (pinfunction "RXD0_15") (pintype "input"))
      (node (ref "U4") (pin "2") (pinfunction "TXD_2") (pintype "input"))
    )
    (net (code "39") (name "SC0") (class "Default")
      (node (ref "R2") (pin "2") (pinfunction "2_2") (pintype "input"))
      (node (ref "RJ1") (pin "6") (pinfunction "6_6") (pintype "input"))
      (node (ref "U2") (pin "5") (pinfunction "SC0_5") (pintype "input"))
    )
    (net (code "40") (name "SC1") (class "Default")
      (node (ref "R25") (pin "2") (pinfunction "2_2") (pintype "input"))
      (node (ref "RJ2") (pin "6") (pinfunction "6_6") (pintype "input"))
      (node (ref "U2") (pin "7") (pinfunction "SC1_7") (pintype "input"))
    )
    (net (code "41") (name "SC2") (class "Default")
      (node (ref "R27") (pin "2") (pinfunction "2_2") (pintype "input"))
      (node (ref "RJ4") (pin "6") (pinfunction "6_6") (pintype "input"))
      (node (ref "U2") (pin "9") (pinfunction "SC2_9") (pintype "input"))
    )
    (net (code "42") (name "SC3") (class "Default")
      (node (ref "R29") (pin "2") (pinfunction "2_2") (pintype "input"))
      (node (ref "RJ3") (pin "6") (pinfunction "6_6") (pintype "input"))
      (node (ref "U2") (pin "11") (pinfunction "SC3_11") (pintype "input"))
    )
    (net (code "43") (name "SC4") (class "Default")
      (node (ref "R31") (pin "2") (pinfunction "2_2") (pintype "input"))
      (node (ref "RJ8") (pin "6") (pinfunction "6_6") (pintype "input"))
      (node (ref "U2") (pin "14") (pinfunction "SC4_14") (pintype "input"))
    )
    (net (code "44") (name "SC5") (class "Default")
      (node (ref "R33") (pin "2") (pinfunction "2_2") (pintype "input"))
      (node (ref "RJ7") (pin "6") (pinfunction "6_6") (pintype "input"))
      (node (ref "U2") (pin "16") (pinfunction "SC5_16") (pintype "input"))
    )
    (net (code "45") (name "SC6") (class "Default")
      (node (ref "R35") (pin "2") (pinfunction "2_2") (pintype "input"))
      (node (ref "RJ5") (pin "6") (pinfunction "6_6") (pintype "input"))
      (node (ref "U2") (pin "18") (pinfunction "SC6_18") (pintype "input"))
    )
    (net (code "46") (name "SC7") (class "Default")
      (node (ref "R37") (pin "2") (pinfunction "2_2") (pintype "input"))
      (node (ref "RJ6") (pin "6") (pinfunction "6_6") (pintype "input"))
      (node (ref "U2") (pin "20") (pinfunction "SC7_20") (pintype "input"))
    )
    (net (code "47") (name "SCL") (class "Default")
      (node (ref "J1") (pin "3") (pinfunction "3_3") (pintype "input"))
      (node (ref "R10") (pin "2") (pinfunction "2_2") (pintype "input"))
      (node (ref "U1") (pin "14") (pinfunction "GPIO5_14") (pintype "input"))
      (node (ref "U2") (pin "22") (pinfunction "SCL_22") (pintype "input"))
    )
    (net (code "48") (name "SD0") (class "Default")
      (node (ref "R23") (pin "2") (pinfunction "2_2") (pintype "input"))
      (node (ref "RJ1") (pin "3") (pinfunction "3_3") (pintype "input"))
      (node (ref "U2") (pin "4") (pinfunction "SD0_4") (pintype "input"))
    )
    (net (code "49") (name "SD1") (class "Default")
      (node (ref "R24") (pin "2") (pinfunction "2_2") (pintype "input"))
      (node (ref "RJ2") (pin "3") (pinfunction "3_3") (pintype "input"))
      (node (ref "U2") (pin "6") (pinfunction "SD1_6") (pintype "input"))
    )
    (net (code "50") (name "SD2") (class "Default")
      (node (ref "R26") (pin "2") (pinfunction "2_2") (pintype "input"))
      (node (ref "RJ4") (pin "3") (pinfunction "3_3") (pintype "input"))
      (node (ref "U2") (pin "8") (pinfunction "SD2_8") (pintype "input"))
    )
    (net (code "51") (name "SD3") (class "Default")
      (node (ref "R28") (pin "2") (pinfunction "2_2") (pintype "input"))
      (node (ref "RJ3") (pin "3") (pinfunction "3_3") (pintype "input"))
      (node (ref "U2") (pin "10") (pinfunction "SD3_10") (pintype "input"))
    )
    (net (code "52") (name "SD4") (class "Default")
      (node (ref "R30") (pin "2") (pinfunction "2_2") (pintype "input"))
      (node (ref "RJ8") (pin "3") (pinfunction "3_3") (pintype "input"))
      (node (ref "U2") (pin "13") (pinfunction "SD4_13") (pintype "input"))
    )
    (net (code "53") (name "SD5") (class "Default")
      (node (ref "R32") (pin "2") (pinfunction "2_2") (pintype "input"))
      (node (ref "RJ7") (pin "3") (pinfunction "3_3") (pintype "input"))
      (node (ref "U2") (pin "15") (pinfunction "SD5_15") (pintype "input"))
    )
    (net (code "54") (name "SD6") (class "Default")
      (node (ref "R34") (pin "2") (pinfunction "2_2") (pintype "input"))
      (node (ref "RJ5") (pin "3") (pinfunction "3_3") (pintype "input"))
      (node (ref "U2") (pin "17") (pinfunction "SD6_17") (pintype "input"))
    )
    (net (code "55") (name "SD7") (class "Default")
      (node (ref "R36") (pin "2") (pinfunction "2_2") (pintype "input"))
      (node (ref "RJ6") (pin "3") (pinfunction "3_3") (pintype "input"))
      (node (ref "U2") (pin "19") (pinfunction "SD7_19") (pintype "input"))
    )
    (net (code "56") (name "SDA") (class "Default")
      (node (ref "J1") (pin "4") (pinfunction "4_4") (pintype "input"))
      (node (ref "R12") (pin "2") (pinfunction "2_2") (pintype "input"))
      (node (ref "U1") (pin "13") (pinfunction "GPIO4_13") (pintype "input"))
      (node (ref "U2") (pin "23") (pinfunction "SDA_23") (pintype "input"))
    )
    (net (code "57") (name "TX") (class "Default")
      (node (ref "R21") (pin "1") (pinfunction "1_1") (pintype "input"))
      (node (ref "U1") (pin "16") (pinfunction "TXD0_16") (pintype "input"))
    )
    (net (code "58") (name "unconnected-(Q2-D12-Pad2)") (class "Default")
      (node (ref "Q2") (pin "2") (pinfunction "D12_2") (pintype "input+no_connect"))
    )
    (net (code "59") (name "unconnected-(Q2-D12-Pad5)") (class "Default")
      (node (ref "Q2") (pin "5") (pinfunction "D12_5") (pintype "input+no_connect"))
    )
    (net (code "60") (name "unconnected-(Q3-NC-Pad4)") (class "Default")
      (node (ref "Q3") (pin "4") (pinfunction "NC_4") (pintype "input+no_connect"))
    )
    (net (code "61") (name "unconnected-(RJ1-Pad2)") (class "Default")
      (node (ref "RJ1") (pin "2") (pinfunction "2_2") (pintype "input+no_connect"))
    )
    (net (code "62") (name "unconnected-(RJ1-Pad4)") (class "Default")
      (node (ref "RJ1") (pin "4") (pinfunction "4_4") (pintype "input+no_connect"))
    )
    (net (code "63") (name "unconnected-(RJ1-Pad5)") (class "Default")
      (node (ref "RJ1") (pin "5") (pinfunction "5_5") (pintype "input+no_connect"))
    )
    (net (code "64") (name "unconnected-(RJ1-Pad7)") (class "Default")
      (node (ref "RJ1") (pin "7") (pinfunction "7_7") (pintype "input+no_connect"))
    )
    (net (code "65") (name "unconnected-(RJ2-Pad2)") (class "Default")
      (node (ref "RJ2") (pin "2") (pinfunction "2_2") (pintype "input+no_connect"))
    )
    (net (code "66") (name "unconnected-(RJ2-Pad4)") (class "Default")
      (node (ref "RJ2") (pin "4") (pinfunction "4_4") (pintype "input+no_connect"))
    )
    (net (code "67") (name "unconnected-(RJ2-Pad5)") (class "Default")
      (node (ref "RJ2") (pin "5") (pinfunction "5_5") (pintype "input+no_connect"))
    )
    (net (code "68") (name "unconnected-(RJ2-Pad7)") (class "Default")
      (node (ref "RJ2") (pin "7") (pinfunction "7_7") (pintype "input+no_connect"))
    )
    (net (code "69") (name "unconnected-(RJ3-Pad2)") (class "Default")
      (node (ref "RJ3") (pin "2") (pinfunction "2_2") (pintype "input+no_connect"))
    )
    (net (code "70") (name "unconnected-(RJ3-Pad4)") (class "Default")
      (node (ref "RJ3") (pin "4") (pinfunction "4_4") (pintype "input+no_connect"))
    )
    (net (code "71") (name "unconnected-(RJ3-Pad5)") (class "Default")
      (node (ref "RJ3") (pin "5") (pinfunction "5_5") (pintype "input+no_connect"))
    )
    (net (code "72") (name "unconnected-(RJ3-Pad7)") (class "Default")
      (node (ref "RJ3") (pin "7") (pinfunction "7_7") (pintype "input+no_connect"))
    )
    (net (code "73") (name "unconnected-(RJ4-Pad2)") (class "Default")
      (node (ref "RJ4") (pin "2") (pinfunction "2_2") (pintype "input+no_connect"))
    )
    (net (code "74") (name "unconnected-(RJ4-Pad4)") (class "Default")
      (node (ref "RJ4") (pin "4") (pinfunction "4_4") (pintype "input+no_connect"))
    )
    (net (code "75") (name "unconnected-(RJ4-Pad5)") (class "Default")
      (node (ref "RJ4") (pin "5") (pinfunction "5_5") (pintype "input+no_connect"))
    )
    (net (code "76") (name "unconnected-(RJ4-Pad7)") (class "Default")
      (node (ref "RJ4") (pin "7") (pinfunction "7_7") (pintype "input+no_connect"))
    )
    (net (code "77") (name "unconnected-(RJ5-Pad2)") (class "Default")
      (node (ref "RJ5") (pin "2") (pinfunction "2_2") (pintype "input+no_connect"))
    )
    (net (code "78") (name "unconnected-(RJ5-Pad4)") (class "Default")
      (node (ref "RJ5") (pin "4") (pinfunction "4_4") (pintype "input+no_connect"))
    )
    (net (code "79") (name "unconnected-(RJ5-Pad5)") (class "Default")
      (node (ref "RJ5") (pin "5") (pinfunction "5_5") (pintype "input+no_connect"))
    )
    (net (code "80") (name "unconnected-(RJ5-Pad7)") (class "Default")
      (node (ref "RJ5") (pin "7") (pinfunction "7_7") (pintype "input+no_connect"))
    )
    (net (code "81") (name "unconnected-(RJ6-Pad2)") (class "Default")
      (node (ref "RJ6") (pin "2") (pinfunction "2_2") (pintype "input+no_connect"))
    )
    (net (code "82") (name "unconnected-(RJ6-Pad4)") (class "Default")
      (node (ref "RJ6") (pin "4") (pinfunction "4_4") (pintype "input+no_connect"))
    )
    (net (code "83") (name "unconnected-(RJ6-Pad5)") (class "Default")
      (node (ref "RJ6") (pin "5") (pinfunction "5_5") (pintype "input+no_connect"))
    )
    (net (code "84") (name "unconnected-(RJ6-Pad7)") (class "Default")
      (node (ref "RJ6") (pin "7") (pinfunction "7_7") (pintype "input+no_connect"))
    )
    (net (code "85") (name "unconnected-(RJ7-Pad2)") (class "Default")
      (node (ref "RJ7") (pin "2") (pinfunction "2_2") (pintype "input+no_connect"))
    )
    (net (code "86") (name "unconnected-(RJ7-Pad4)") (class "Default")
      (node (ref "RJ7") (pin "4") (pinfunction "4_4") (pintype "input+no_connect"))
    )
    (net (code "87") (name "unconnected-(RJ7-Pad5)") (class "Default")
      (node (ref "RJ7") (pin "5") (pinfunction "5_5") (pintype "input+no_connect"))
    )
    (net (code "88") (name "unconnected-(RJ7-Pad7)") (class "Default")
      (node (ref "RJ7") (pin "7") (pinfunction "7_7") (pintype "input+no_connect"))
    )
    (net (code "89") (name "unconnected-(RJ8-Pad2)") (class "Default")
      (node (ref "RJ8") (pin "2") (pinfunction "2_2") (pintype "input+no_connect"))
    )
    (net (code "90") (name "unconnected-(RJ8-Pad4)") (class "Default")
      (node (ref "RJ8") (pin "4") (pinfunction "4_4") (pintype "input+no_connect"))
    )
    (net (code "91") (name "unconnected-(RJ8-Pad5)") (class "Default")
      (node (ref "RJ8") (pin "5") (pinfunction "5_5") (pintype "input+no_connect"))
    )
    (net (code "92") (name "unconnected-(RJ8-Pad7)") (class "Default")
      (node (ref "RJ8") (pin "7") (pinfunction "7_7") (pintype "input+no_connect"))
    )
    (net (code "93") (name "unconnected-(U1-CS0-Pad17)") (class "Default")
      (node (ref "U1") (pin "17") (pinfunction "CS0_17") (pintype "input+no_connect"))
    )
    (net (code "94") (name "unconnected-(U1-GPIO9-Pad19)") (class "Default")
      (node (ref "U1") (pin "19") (pinfunction "GPIO9_19") (pintype "input+no_connect"))
    )
    (net (code "95") (name "unconnected-(U1-GPIO10-Pad20)") (class "Default")
      (node (ref "U1") (pin "20") (pinfunction "GPIO10_20") (pintype "input+no_connect"))
    )
    (net (code "96") (name "unconnected-(U1-GPIO16-Pad4)") (class "Default")
      (node (ref "U1") (pin "4") (pinfunction "GPIO16_4") (pintype "input+no_connect"))
    )
    (net (code "97") (name "unconnected-(U1-MISO-Pad18)") (class "Default")
      (node (ref "U1") (pin "18") (pinfunction "MISO_18") (pintype "input+no_connect"))
    )
    (net (code "98") (name "unconnected-(U1-MOSI-Pad21)") (class "Default")
      (node (ref "U1") (pin "21") (pinfunction "MOSI_21") (pintype "input+no_connect"))
    )
    (net (code "99") (name "unconnected-(U1-SCLK-Pad22)") (class "Default")
      (node (ref "U1") (pin "22") (pinfunction "SCLK_22") (pintype "input+no_connect"))
    )
    (net (code "100") (name "unconnected-(U4-CTS#-Pad9)") (class "Default")
      (node (ref "U4") (pin "9") (pinfunction "CTS#_9") (pintype "input+no_connect"))
    )
    (net (code "101") (name "unconnected-(U4-DCD#-Pad12)") (class "Default")
      (node (ref "U4") (pin "12") (pinfunction "DCD#_12") (pintype "input+no_connect"))
    )
    (net (code "102") (name "unconnected-(U4-DSR#-Pad10)") (class "Default")
      (node (ref "U4") (pin "10") (pinfunction "DSR#_10") (pintype "input+no_connect"))
    )
    (net (code "103") (name "unconnected-(U4-NC.-Pad7)") (class "Default")
      (node (ref "U4") (pin "7") (pinfunction "NC._7") (pintype "input+no_connect"))
    )
    (net (code "104") (name "unconnected-(U4-NC.-Pad8)") (class "Default")
      (node (ref "U4") (pin "8") (pinfunction "NC._8") (pintype "input+no_connect"))
    )
    (net (code "105") (name "unconnected-(U4-R232-Pad15)") (class "Default")
      (node (ref "U4") (pin "15") (pinfunction "R232_15") (pintype "input+no_connect"))
    )
    (net (code "106") (name "unconnected-(U4-RI#-Pad11)") (class "Default")
      (node (ref "U4") (pin "11") (pinfunction "RI#_11") (pintype "input+no_connect"))
    )
    (net (code "107") (name "unconnected-(U6-TD-Pad4)") (class "Default")
      (node (ref "U6") (pin "4") (pinfunction "TD_4") (pintype "input+no_connect"))
    )
    (net (code "108") (name "unconnected-(USB1-SBU1-PadA8)") (class "Default")
      (node (ref "USB1") (pin "A8") (pinfunction "SBU1_A8") (pintype "input+no_connect"))
    )
    (net (code "109") (name "unconnected-(USB1-SBU2-PadB8)") (class "Default")
      (node (ref "USB1") (pin "B8") (pinfunction "SBU2_B8") (pintype "input+no_connect"))
    )
  )
)
